# M302.net
KiCad netlist of a schematic drawn in EAGLE
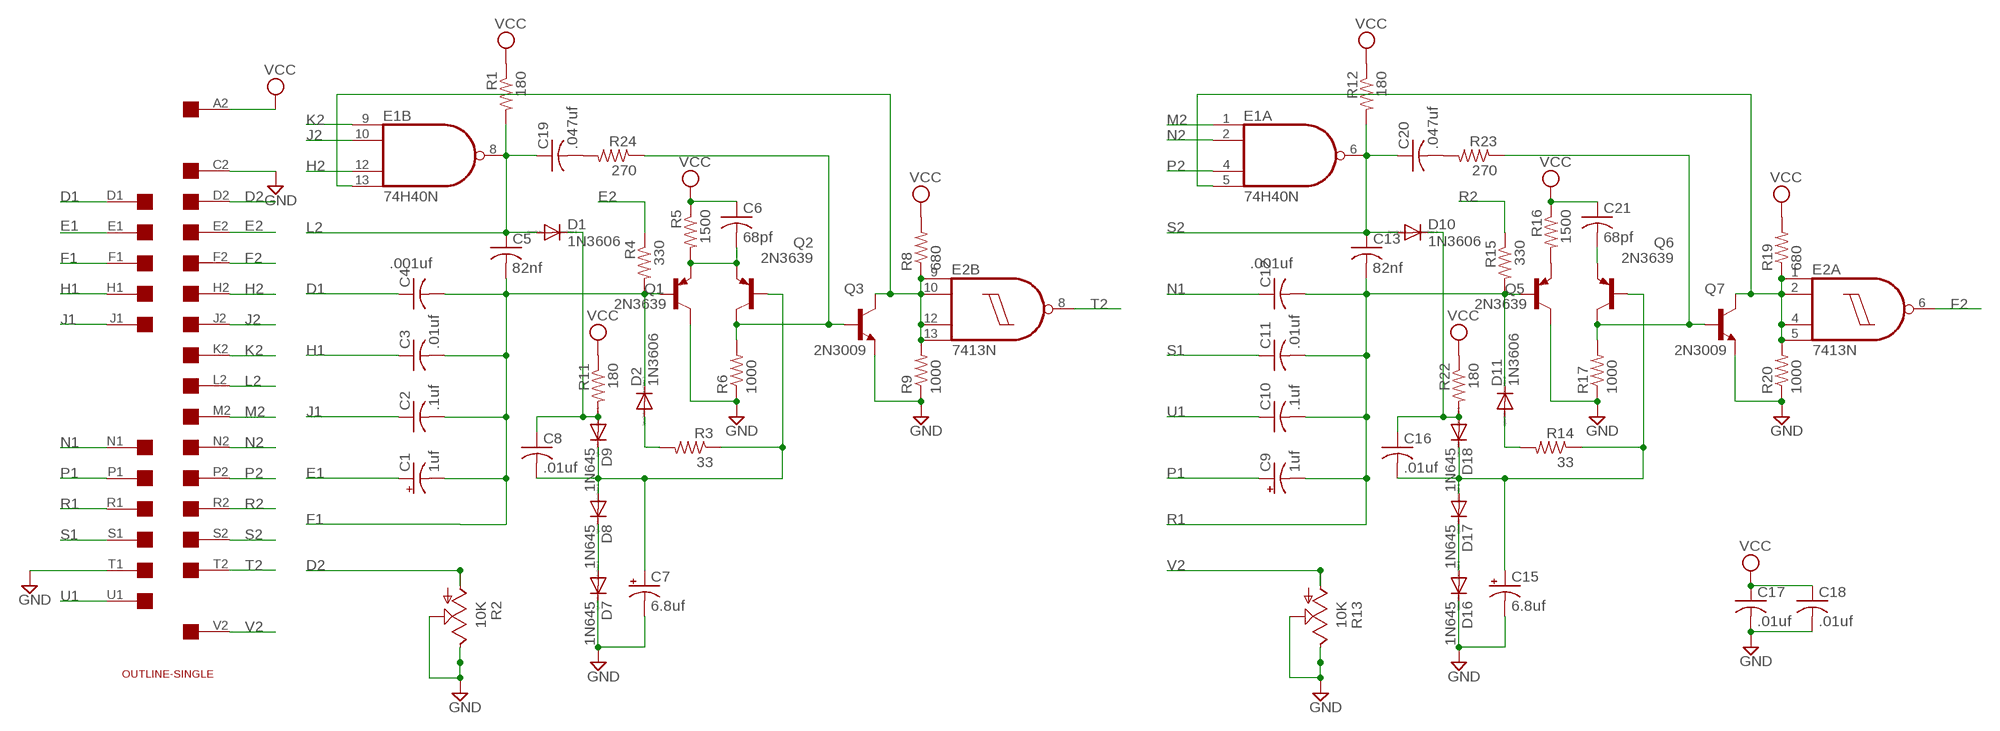
[diagram p0: schematic, sheet 1]

(export (version "E")
  (design (tool "Eeschema 10.0.6"))
  (components
    (comp (ref "C1")
      (value "1uf")
      (footprint "eagle-import:E15-5")
      (libsource (lib "eagle-import") (part "CPOL-USE15-5AXIAL"))
    )
    (comp (ref "C2")
      (value ".1uf")
      (footprint "eagle-import:C050-025X075")
      (libsource (lib "eagle-import") (part "C-US050-025X075"))
    )
    (comp (ref "C3")
      (value ".01uf")
      (footprint "eagle-import:C050-025X075")
      (libsource (lib "eagle-import") (part "C-US050-025X075"))
    )
    (comp (ref "C4")
      (value ".001uf")
      (footprint "eagle-import:C050-025X075")
      (libsource (lib "eagle-import") (part "C-US050-025X075"))
    )
    (comp (ref "C5")
      (value "82nf")
      (footprint "eagle-import:C050-025X075")
      (libsource (lib "eagle-import") (part "C-US050-025X075"))
    )
    (comp (ref "C6")
      (value "68pf")
      (footprint "eagle-import:C050-025X075")
      (libsource (lib "eagle-import") (part "C-US050-025X075"))
    )
    (comp (ref "C7")
      (value "6.8uf")
      (footprint "eagle-import:E15-5")
      (libsource (lib "eagle-import") (part "CPOL-USE15-5AXIAL"))
    )
    (comp (ref "C8")
      (value ".01uf")
      (footprint "eagle-import:C050-025X075")
      (libsource (lib "eagle-import") (part "C-US050-025X075"))
    )
    (comp (ref "C9")
      (value "1uf")
      (footprint "eagle-import:E15-5")
      (libsource (lib "eagle-import") (part "CPOL-USE15-5AXIAL"))
    )
    (comp (ref "C10")
      (value ".1uf")
      (footprint "eagle-import:C050-025X075")
      (libsource (lib "eagle-import") (part "C-US050-025X075"))
    )
    (comp (ref "C11")
      (value ".01uf")
      (footprint "eagle-import:C050-025X075")
      (libsource (lib "eagle-import") (part "C-US050-025X075"))
    )
    (comp (ref "C12")
      (value ".001uf")
      (footprint "eagle-import:C050-025X075")
      (libsource (lib "eagle-import") (part "C-US050-025X075"))
    )
    (comp (ref "C13")
      (value "82nf")
      (footprint "eagle-import:C050-025X075")
      (libsource (lib "eagle-import") (part "C-US050-025X075"))
    )
    (comp (ref "C15")
      (value "6.8uf")
      (footprint "eagle-import:E15-5")
      (libsource (lib "eagle-import") (part "CPOL-USE15-5AXIAL"))
    )
    (comp (ref "C16")
      (value ".01uf")
      (footprint "eagle-import:C050-025X075")
      (libsource (lib "eagle-import") (part "C-US050-025X075"))
    )
    (comp (ref "C17")
      (value ".01uf")
      (footprint "eagle-import:C050-025X075")
      (libsource (lib "eagle-import") (part "C-US050-025X075"))
    )
    (comp (ref "C18")
      (value ".01uf")
      (footprint "eagle-import:C050-025X075")
      (libsource (lib "eagle-import") (part "C-US050-025X075"))
    )
    (comp (ref "C19")
      (value ".047uf")
      (footprint "eagle-import:C050-025X075")
      (libsource (lib "eagle-import") (part "C-US050-025X075"))
    )
    (comp (ref "C20")
      (value ".047uf")
      (footprint "eagle-import:C050-025X075")
      (libsource (lib "eagle-import") (part "C-US050-025X075"))
    )
    (comp (ref "C21")
      (value "68pf")
      (footprint "eagle-import:C050-025X075")
      (libsource (lib "eagle-import") (part "C-US050-025X075"))
    )
    (comp (ref "D1")
      (value "1N3606")
      (footprint "eagle-import:DO35-10")
      (libsource (lib "eagle-import") (part "1N4148DO35-10"))
    )
    (comp (ref "D2")
      (value "1N3606")
      (footprint "eagle-import:DO35-10")
      (libsource (lib "eagle-import") (part "1N4148DO35-10"))
    )
    (comp (ref "D7")
      (value "1N645")
      (footprint "eagle-import:DO35-10")
      (libsource (lib "eagle-import") (part "1N4148DO35-10"))
    )
    (comp (ref "D8")
      (value "1N645")
      (footprint "eagle-import:DO35-10")
      (libsource (lib "eagle-import") (part "1N4148DO35-10"))
    )
    (comp (ref "D9")
      (value "1N645")
      (footprint "eagle-import:DO35-10")
      (libsource (lib "eagle-import") (part "1N4148DO35-10"))
    )
    (comp (ref "D10")
      (value "1N3606")
      (footprint "eagle-import:DO35-10")
      (libsource (lib "eagle-import") (part "1N4148DO35-10"))
    )
    (comp (ref "D11")
      (value "1N3606")
      (footprint "eagle-import:DO35-10")
      (libsource (lib "eagle-import") (part "1N4148DO35-10"))
    )
    (comp (ref "D16")
      (value "1N645")
      (footprint "eagle-import:DO35-10")
      (libsource (lib "eagle-import") (part "1N4148DO35-10"))
    )
    (comp (ref "D17")
      (value "1N645")
      (footprint "eagle-import:DO35-10")
      (libsource (lib "eagle-import") (part "1N4148DO35-10"))
    )
    (comp (ref "D18")
      (value "1N645")
      (footprint "eagle-import:DO35-10")
      (libsource (lib "eagle-import") (part "1N4148DO35-10"))
    )
    (comp (ref "E1")
      (value "74H40N")
      (footprint "eagle-import:DIL14")
      (libsource (lib "eagle-import") (part "7420NS"))
    )
    (comp (ref "E2")
      (value "7413N")
      (footprint "eagle-import:DIL14")
      (libsource (lib "eagle-import") (part "7413N"))
    )
    (comp (ref "Q1")
      (value "2N3639")
      (footprint "eagle-import:TO39")
      (libsource (lib "eagle-import") (part "-PNP-TO39-EBC2N3637"))
    )
    (comp (ref "Q2")
      (value "2N3639")
      (footprint "eagle-import:TO39")
      (libsource (lib "eagle-import") (part "-PNP-TO39-EBC2N3637"))
    )
    (comp (ref "Q3")
      (value "2N3009")
      (footprint "eagle-import:TO39")
      (libsource (lib "eagle-import") (part "-NPN-TO39-EBC2N3019"))
    )
    (comp (ref "Q5")
      (value "2N3639")
      (footprint "eagle-import:TO39")
      (libsource (lib "eagle-import") (part "-PNP-TO39-EBC2N3637"))
    )
    (comp (ref "Q6")
      (value "2N3639")
      (footprint "eagle-import:TO39")
      (libsource (lib "eagle-import") (part "-PNP-TO39-EBC2N3637"))
    )
    (comp (ref "Q7")
      (value "2N3009")
      (footprint "eagle-import:TO39")
      (libsource (lib "eagle-import") (part "-NPN-TO39-EBC2N3019"))
    )
    (comp (ref "R1")
      (value "180")
      (footprint "eagle-import:0207_10")
      (libsource (lib "eagle-import") (part "R-US_0207/10"))
    )
    (comp (ref "R2")
      (value "10K")
      (footprint "eagle-import:PT-SPIN")
      (libsource (lib "eagle-import") (part "TRIM_US-PTSPIN"))
    )
    (comp (ref "R3")
      (value "33")
      (footprint "eagle-import:0207_10")
      (libsource (lib "eagle-import") (part "R-US_0207/10"))
    )
    (comp (ref "R4")
      (value "330")
      (footprint "eagle-import:0207_10")
      (libsource (lib "eagle-import") (part "R-US_0207/10"))
    )
    (comp (ref "R5")
      (value "1500")
      (footprint "eagle-import:0207_10")
      (libsource (lib "eagle-import") (part "R-US_0207/10"))
    )
    (comp (ref "R6")
      (value "1000")
      (footprint "eagle-import:0207_10")
      (libsource (lib "eagle-import") (part "R-US_0207/10"))
    )
    (comp (ref "R8")
      (value "680")
      (footprint "eagle-import:0207_10")
      (libsource (lib "eagle-import") (part "R-US_0207/10"))
    )
    (comp (ref "R9")
      (value "1000")
      (footprint "eagle-import:0207_10")
      (libsource (lib "eagle-import") (part "R-US_0207/10"))
    )
    (comp (ref "R11")
      (value "180")
      (footprint "eagle-import:0207_10")
      (libsource (lib "eagle-import") (part "R-US_0207/10"))
    )
    (comp (ref "R12")
      (value "180")
      (footprint "eagle-import:0207_10")
      (libsource (lib "eagle-import") (part "R-US_0207/10"))
    )
    (comp (ref "R13")
      (value "10K")
      (footprint "eagle-import:PT-SPIN")
      (libsource (lib "eagle-import") (part "TRIM_US-PTSPIN"))
    )
    (comp (ref "R14")
      (value "33")
      (footprint "eagle-import:0207_10")
      (libsource (lib "eagle-import") (part "R-US_0207/10"))
    )
    (comp (ref "R15")
      (value "330")
      (footprint "eagle-import:0207_10")
      (libsource (lib "eagle-import") (part "R-US_0207/10"))
    )
    (comp (ref "R16")
      (value "1500")
      (footprint "eagle-import:0207_10")
      (libsource (lib "eagle-import") (part "R-US_0207/10"))
    )
    (comp (ref "R17")
      (value "1000")
      (footprint "eagle-import:0207_10")
      (libsource (lib "eagle-import") (part "R-US_0207/10"))
    )
    (comp (ref "R19")
      (value "680")
      (footprint "eagle-import:0207_10")
      (libsource (lib "eagle-import") (part "R-US_0207/10"))
    )
    (comp (ref "R20")
      (value "1000")
      (footprint "eagle-import:0207_10")
      (libsource (lib "eagle-import") (part "R-US_0207/10"))
    )
    (comp (ref "R22")
      (value "180")
      (footprint "eagle-import:0207_10")
      (libsource (lib "eagle-import") (part "R-US_0207/10"))
    )
    (comp (ref "R23")
      (value "270")
      (footprint "eagle-import:0207_10")
      (libsource (lib "eagle-import") (part "R-US_0207/10"))
    )
    (comp (ref "R24")
      (value "270")
      (footprint "eagle-import:0207_10")
      (libsource (lib "eagle-import") (part "R-US_0207/10"))
    )
    (comp (ref "U$1")
      (value "SINGLE")
      (footprint "eagle-import:EDGE-CON2")
      (libsource (lib "eagle-import") (part "SINGLE"))
    )
    (comp (ref "U$2")
      (value "OUTLINE-SINGLE")
      (footprint "eagle-import:SINGLE")
      (libsource (lib "eagle-import") (part "OUTLINE-SINGLE"))
    )
  )
  (nets
    (net (code "1") (name "/D1") (class "Default")
      (node (ref "C4") (pin "1") (pinfunction "1_1") (pintype "passive"))
      (node (ref "U$1") (pin "D1") (pinfunction "1_D1") (pintype "bidirectional"))
    )
    (net (code "2") (name "/D2") (class "Default")
      (node (ref "R2") (pin "A") (pinfunction "A_A") (pintype "passive"))
      (node (ref "U$1") (pin "D2") (pinfunction "1_D2") (pintype "bidirectional"))
    )
    (net (code "3") (name "/E1") (class "Default")
      (node (ref "C1") (pin "+") (pinfunction "+_+") (pintype "passive"))
      (node (ref "U$1") (pin "E1") (pinfunction "1_E1") (pintype "bidirectional"))
    )
    (net (code "4") (name "/E2") (class "Default")
      (node (ref "R4") (pin "1") (pinfunction "1_1") (pintype "passive"))
      (node (ref "U$1") (pin "E2") (pinfunction "1_E2") (pintype "bidirectional"))
    )
    (net (code "5") (name "/F1") (class "Default")
      (node (ref "C1") (pin "-") (pinfunction "-_-") (pintype "passive"))
      (node (ref "C2") (pin "2") (pinfunction "2_2") (pintype "passive"))
      (node (ref "C3") (pin "2") (pinfunction "2_2") (pintype "passive"))
      (node (ref "C4") (pin "2") (pinfunction "2_2") (pintype "passive"))
      (node (ref "C5") (pin "2") (pinfunction "2_2") (pintype "passive"))
      (node (ref "D2") (pin "C") (pinfunction "C_C") (pintype "passive"))
      (node (ref "Q1") (pin "2") (pinfunction "B_2") (pintype "passive"))
      (node (ref "R4") (pin "2") (pinfunction "2_2") (pintype "passive"))
      (node (ref "U$1") (pin "F1") (pinfunction "1_F1") (pintype "bidirectional"))
    )
    (net (code "6") (name "/F2") (class "Default")
      (node (ref "E2") (pin "6") (pinfunction "O_6") (pintype "output"))
      (node (ref "U$1") (pin "F2") (pinfunction "1_F2") (pintype "bidirectional"))
    )
    (net (code "7") (name "/H1") (class "Default")
      (node (ref "C3") (pin "1") (pinfunction "1_1") (pintype "passive"))
      (node (ref "U$1") (pin "H1") (pinfunction "1_H1") (pintype "bidirectional"))
    )
    (net (code "8") (name "/H2") (class "Default")
      (node (ref "E1") (pin "12") (pinfunction "I2_12") (pintype "input"))
      (node (ref "U$1") (pin "H2") (pinfunction "1_H2") (pintype "bidirectional"))
    )
    (net (code "9") (name "/J1") (class "Default")
      (node (ref "C2") (pin "1") (pinfunction "1_1") (pintype "passive"))
      (node (ref "U$1") (pin "J1") (pinfunction "1_J1") (pintype "bidirectional"))
    )
    (net (code "10") (name "/J2") (class "Default")
      (node (ref "E1") (pin "10") (pinfunction "I1_10") (pintype "input"))
      (node (ref "U$1") (pin "J2") (pinfunction "1_J2") (pintype "bidirectional"))
    )
    (net (code "11") (name "/K2") (class "Default")
      (node (ref "E1") (pin "9") (pinfunction "I0_9") (pintype "input"))
      (node (ref "U$1") (pin "K2") (pinfunction "1_K2") (pintype "bidirectional"))
    )
    (net (code "12") (name "/L2") (class "Default")
      (node (ref "C19") (pin "1") (pinfunction "1_1") (pintype "passive"))
      (node (ref "C5") (pin "1") (pinfunction "1_1") (pintype "passive"))
      (node (ref "D1") (pin "A") (pinfunction "A_A") (pintype "passive"))
      (node (ref "E1") (pin "8") (pinfunction "O_8") (pintype "output"))
      (node (ref "R1") (pin "2") (pinfunction "2_2") (pintype "passive"))
      (node (ref "U$1") (pin "L2") (pinfunction "1_L2") (pintype "bidirectional"))
    )
    (net (code "13") (name "/M2") (class "Default")
      (node (ref "E1") (pin "1") (pinfunction "I0_1") (pintype "input"))
      (node (ref "U$1") (pin "M2") (pinfunction "1_M2") (pintype "bidirectional"))
    )
    (net (code "14") (name "/N1") (class "Default")
      (node (ref "C12") (pin "1") (pinfunction "1_1") (pintype "passive"))
      (node (ref "U$1") (pin "N1") (pinfunction "1_N1") (pintype "bidirectional"))
    )
    (net (code "15") (name "/N2") (class "Default")
      (node (ref "E1") (pin "2") (pinfunction "I1_2") (pintype "input"))
      (node (ref "U$1") (pin "N2") (pinfunction "1_N2") (pintype "bidirectional"))
    )
    (net (code "16") (name "/P1") (class "Default")
      (node (ref "C9") (pin "+") (pinfunction "+_+") (pintype "passive"))
      (node (ref "U$1") (pin "P1") (pinfunction "1_P1") (pintype "bidirectional"))
    )
    (net (code "17") (name "/P2") (class "Default")
      (node (ref "E1") (pin "4") (pinfunction "I2_4") (pintype "input"))
      (node (ref "U$1") (pin "P2") (pinfunction "1_P2") (pintype "bidirectional"))
    )
    (net (code "18") (name "/R1") (class "Default")
      (node (ref "C10") (pin "2") (pinfunction "2_2") (pintype "passive"))
      (node (ref "C11") (pin "2") (pinfunction "2_2") (pintype "passive"))
      (node (ref "C12") (pin "2") (pinfunction "2_2") (pintype "passive"))
      (node (ref "C13") (pin "2") (pinfunction "2_2") (pintype "passive"))
      (node (ref "C9") (pin "-") (pinfunction "-_-") (pintype "passive"))
      (node (ref "D11") (pin "C") (pinfunction "C_C") (pintype "passive"))
      (node (ref "Q5") (pin "2") (pinfunction "B_2") (pintype "passive"))
      (node (ref "R15") (pin "2") (pinfunction "2_2") (pintype "passive"))
      (node (ref "U$1") (pin "R1") (pinfunction "1_R1") (pintype "bidirectional"))
    )
    (net (code "19") (name "/R2") (class "Default")
      (node (ref "R15") (pin "1") (pinfunction "1_1") (pintype "passive"))
      (node (ref "U$1") (pin "R2") (pinfunction "1_R2") (pintype "bidirectional"))
    )
    (net (code "20") (name "/S1") (class "Default")
      (node (ref "C11") (pin "1") (pinfunction "1_1") (pintype "passive"))
      (node (ref "U$1") (pin "S1") (pinfunction "1_S1") (pintype "bidirectional"))
    )
    (net (code "21") (name "/S2") (class "Default")
      (node (ref "C13") (pin "1") (pinfunction "1_1") (pintype "passive"))
      (node (ref "C20") (pin "1") (pinfunction "1_1") (pintype "passive"))
      (node (ref "D10") (pin "A") (pinfunction "A_A") (pintype "passive"))
      (node (ref "E1") (pin "6") (pinfunction "O_6") (pintype "output"))
      (node (ref "R12") (pin "2") (pinfunction "2_2") (pintype "passive"))
      (node (ref "U$1") (pin "S2") (pinfunction "1_S2") (pintype "bidirectional"))
    )
    (net (code "22") (name "/T2") (class "Default")
      (node (ref "E2") (pin "8") (pinfunction "O_8") (pintype "output"))
      (node (ref "U$1") (pin "T2") (pinfunction "1_T2") (pintype "bidirectional"))
    )
    (net (code "23") (name "/U1") (class "Default")
      (node (ref "C10") (pin "1") (pinfunction "1_1") (pintype "passive"))
      (node (ref "U$1") (pin "U1") (pinfunction "1_U1") (pintype "bidirectional"))
    )
    (net (code "24") (name "/V2") (class "Default")
      (node (ref "R13") (pin "A") (pinfunction "A_A") (pintype "passive"))
      (node (ref "U$1") (pin "V2") (pinfunction "1_V2") (pintype "bidirectional"))
    )
    (net (code "25") (name "GND") (class "Default")
      (node (ref "C15") (pin "-") (pinfunction "-_-") (pintype "passive"))
      (node (ref "C17") (pin "2") (pinfunction "2_2") (pintype "passive"))
      (node (ref "C18") (pin "2") (pinfunction "2_2") (pintype "passive"))
      (node (ref "C7") (pin "-") (pinfunction "-_-") (pintype "passive"))
      (node (ref "D16") (pin "C") (pinfunction "C_C") (pintype "passive"))
      (node (ref "D7") (pin "C") (pinfunction "C_C") (pintype "passive"))
      (node (ref "Q1") (pin "3") (pinfunction "C_3") (pintype "passive"))
      (node (ref "Q3") (pin "1") (pinfunction "E_1") (pintype "passive"))
      (node (ref "Q5") (pin "3") (pinfunction "C_3") (pintype "passive"))
      (node (ref "Q7") (pin "1") (pinfunction "E_1") (pintype "passive"))
      (node (ref "R13") (pin "E") (pinfunction "E_E") (pintype "passive"))
      (node (ref "R13") (pin "S") (pinfunction "S_S") (pintype "passive"))
      (node (ref "R17") (pin "1") (pinfunction "1_1") (pintype "passive"))
      (node (ref "R2") (pin "E") (pinfunction "E_E") (pintype "passive"))
      (node (ref "R2") (pin "S") (pinfunction "S_S") (pintype "passive"))
      (node (ref "R20") (pin "1") (pinfunction "1_1") (pintype "passive"))
      (node (ref "R6") (pin "1") (pinfunction "1_1") (pintype "passive"))
      (node (ref "R9") (pin "1") (pinfunction "1_1") (pintype "passive"))
      (node (ref "U$1") (pin "C2") (pinfunction "1_C2") (pintype "bidirectional"))
      (node (ref "U$1") (pin "T1") (pinfunction "1_T1") (pintype "bidirectional"))
    )
    (net (code "26") (name "Net-(C8-Pad1)") (class "Default")
      (node (ref "C8") (pin "1") (pinfunction "1_1") (pintype "passive"))
      (node (ref "D1") (pin "C") (pinfunction "C_C") (pintype "passive"))
      (node (ref "D9") (pin "A") (pinfunction "A_A") (pintype "passive"))
      (node (ref "R11") (pin "2") (pinfunction "2_2") (pintype "passive"))
    )
    (net (code "27") (name "Net-(C16-Pad1)") (class "Default")
      (node (ref "C16") (pin "1") (pinfunction "1_1") (pintype "passive"))
      (node (ref "D10") (pin "C") (pinfunction "C_C") (pintype "passive"))
      (node (ref "D18") (pin "A") (pinfunction "A_A") (pintype "passive"))
      (node (ref "R22") (pin "2") (pinfunction "2_2") (pintype "passive"))
    )
    (net (code "28") (name "Net-(C19-Pad2)") (class "Default")
      (node (ref "C19") (pin "2") (pinfunction "2_2") (pintype "passive"))
      (node (ref "R24") (pin "2") (pinfunction "2_2") (pintype "passive"))
    )
    (net (code "29") (name "Net-(C20-Pad2)") (class "Default")
      (node (ref "C20") (pin "2") (pinfunction "2_2") (pintype "passive"))
      (node (ref "R23") (pin "2") (pinfunction "2_2") (pintype "passive"))
    )
    (net (code "30") (name "Net-(D2-PadA)") (class "Default")
      (node (ref "D2") (pin "A") (pinfunction "A_A") (pintype "passive"))
      (node (ref "R3") (pin "2") (pinfunction "2_2") (pintype "passive"))
    )
    (net (code "31") (name "Net-(D7-PadA)") (class "Default")
      (node (ref "D7") (pin "A") (pinfunction "A_A") (pintype "passive"))
      (node (ref "D8") (pin "C") (pinfunction "C_C") (pintype "passive"))
    )
    (net (code "32") (name "Net-(D11-PadA)") (class "Default")
      (node (ref "D11") (pin "A") (pinfunction "A_A") (pintype "passive"))
      (node (ref "R14") (pin "2") (pinfunction "2_2") (pintype "passive"))
    )
    (net (code "33") (name "Net-(D16-PadA)") (class "Default")
      (node (ref "D16") (pin "A") (pinfunction "A_A") (pintype "passive"))
      (node (ref "D17") (pin "C") (pinfunction "C_C") (pintype "passive"))
    )
    (net (code "34") (name "Net-(E1A-I3)") (class "Default")
      (node (ref "E1") (pin "5") (pinfunction "I3_5") (pintype "input"))
      (node (ref "E2") (pin "1") (pinfunction "I0_1") (pintype "input"))
      (node (ref "E2") (pin "2") (pinfunction "I1_2") (pintype "input"))
      (node (ref "E2") (pin "4") (pinfunction "I2_4") (pintype "input"))
      (node (ref "E2") (pin "5") (pinfunction "I3_5") (pintype "input"))
      (node (ref "Q7") (pin "3") (pinfunction "C_3") (pintype "passive"))
      (node (ref "R19") (pin "1") (pinfunction "1_1") (pintype "passive"))
      (node (ref "R20") (pin "2") (pinfunction "2_2") (pintype "passive"))
    )
    (net (code "35") (name "Net-(E1B-I3)") (class "Default")
      (node (ref "E1") (pin "13") (pinfunction "I3_13") (pintype "input"))
      (node (ref "E2") (pin "10") (pinfunction "I1_10") (pintype "input"))
      (node (ref "E2") (pin "12") (pinfunction "I2_12") (pintype "input"))
      (node (ref "E2") (pin "13") (pinfunction "I3_13") (pintype "input"))
      (node (ref "E2") (pin "9") (pinfunction "I0_9") (pintype "input"))
      (node (ref "Q3") (pin "3") (pinfunction "C_3") (pintype "passive"))
      (node (ref "R8") (pin "1") (pinfunction "1_1") (pintype "passive"))
      (node (ref "R9") (pin "2") (pinfunction "2_2") (pintype "passive"))
    )
    (net (code "36") (name "Net-(Q1-E)") (class "Default")
      (node (ref "C6") (pin "2") (pinfunction "2_2") (pintype "passive"))
      (node (ref "Q1") (pin "1") (pinfunction "E_1") (pintype "passive"))
      (node (ref "Q2") (pin "1") (pinfunction "E_1") (pintype "passive"))
      (node (ref "R5") (pin "2") (pinfunction "2_2") (pintype "passive"))
    )
    (net (code "37") (name "Net-(Q2-B)") (class "Default")
      (node (ref "C7") (pin "+") (pinfunction "+_+") (pintype "passive"))
      (node (ref "C8") (pin "2") (pinfunction "2_2") (pintype "passive"))
      (node (ref "D8") (pin "A") (pinfunction "A_A") (pintype "passive"))
      (node (ref "D9") (pin "C") (pinfunction "C_C") (pintype "passive"))
      (node (ref "Q2") (pin "2") (pinfunction "B_2") (pintype "passive"))
      (node (ref "R3") (pin "1") (pinfunction "1_1") (pintype "passive"))
    )
    (net (code "38") (name "Net-(Q2-C)") (class "Default")
      (node (ref "Q2") (pin "3") (pinfunction "C_3") (pintype "passive"))
      (node (ref "Q3") (pin "2") (pinfunction "B_2") (pintype "passive"))
      (node (ref "R24") (pin "1") (pinfunction "1_1") (pintype "passive"))
      (node (ref "R6") (pin "2") (pinfunction "2_2") (pintype "passive"))
    )
    (net (code "39") (name "Net-(Q5-E)") (class "Default")
      (node (ref "Q5") (pin "1") (pinfunction "E_1") (pintype "passive"))
      (node (ref "R16") (pin "2") (pinfunction "2_2") (pintype "passive"))
    )
    (net (code "40") (name "Net-(Q6-B)") (class "Default")
      (node (ref "C15") (pin "+") (pinfunction "+_+") (pintype "passive"))
      (node (ref "C16") (pin "2") (pinfunction "2_2") (pintype "passive"))
      (node (ref "D17") (pin "A") (pinfunction "A_A") (pintype "passive"))
      (node (ref "D18") (pin "C") (pinfunction "C_C") (pintype "passive"))
      (node (ref "Q6") (pin "2") (pinfunction "B_2") (pintype "passive"))
      (node (ref "R14") (pin "1") (pinfunction "1_1") (pintype "passive"))
    )
    (net (code "41") (name "Net-(Q6-C)") (class "Default")
      (node (ref "Q6") (pin "3") (pinfunction "C_3") (pintype "passive"))
      (node (ref "Q7") (pin "2") (pinfunction "B_2") (pintype "passive"))
      (node (ref "R17") (pin "2") (pinfunction "2_2") (pintype "passive"))
      (node (ref "R23") (pin "1") (pinfunction "1_1") (pintype "passive"))
    )
    (net (code "42") (name "Net-(Q6-E)") (class "Default")
      (node (ref "C21") (pin "2") (pinfunction "2_2") (pintype "passive"))
      (node (ref "Q6") (pin "1") (pinfunction "E_1") (pintype "passive"))
    )
    (net (code "43") (name "VCC") (class "Default")
      (node (ref "C17") (pin "1") (pinfunction "1_1") (pintype "passive"))
      (node (ref "C18") (pin "1") (pinfunction "1_1") (pintype "passive"))
      (node (ref "C21") (pin "1") (pinfunction "1_1") (pintype "passive"))
      (node (ref "C6") (pin "1") (pinfunction "1_1") (pintype "passive"))
      (node (ref "R1") (pin "1") (pinfunction "1_1") (pintype "passive"))
      (node (ref "R11") (pin "1") (pinfunction "1_1") (pintype "passive"))
      (node (ref "R12") (pin "1") (pinfunction "1_1") (pintype "passive"))
      (node (ref "R16") (pin "1") (pinfunction "1_1") (pintype "passive"))
      (node (ref "R19") (pin "2") (pinfunction "2_2") (pintype "passive"))
      (node (ref "R22") (pin "1") (pinfunction "1_1") (pintype "passive"))
      (node (ref "R5") (pin "1") (pinfunction "1_1") (pintype "passive"))
      (node (ref "R8") (pin "2") (pinfunction "2_2") (pintype "passive"))
      (node (ref "U$1") (pin "A2") (pinfunction "1_A2") (pintype "bidirectional"))
    )
  )
)
